# Eboard_Powerboard.net
KiCad netlist of a schematic drawn in EAGLE
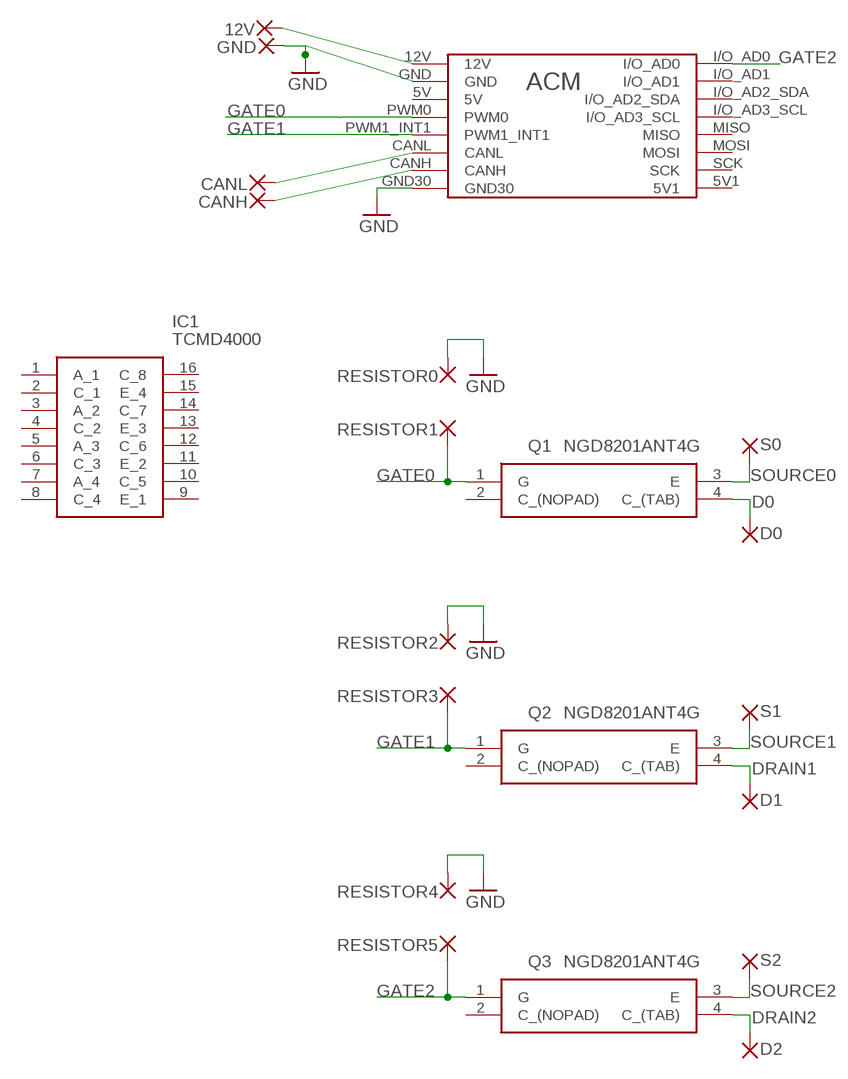
[diagram p0: schematic, sheet 1]

(export (version "E")
  (design (tool "Eeschema 10.0.6"))
  (components
    (comp (ref "12V")
      (value "2,15/1,0")
      (footprint "eagle-import:2,15_1,0")
      (libsource (lib "eagle-import") (part "2,15/1,0"))
    )
    (comp (ref "CANH")
      (value "2,15/1,0")
      (footprint "eagle-import:2,15_1,0")
      (libsource (lib "eagle-import") (part "2,15/1,0"))
    )
    (comp (ref "CANL")
      (value "2,15/1,0")
      (footprint "eagle-import:2,15_1,0")
      (libsource (lib "eagle-import") (part "2,15/1,0"))
    )
    (comp (ref "D0")
      (value "2,54/1,0")
      (footprint "eagle-import:2,54_1,0")
      (libsource (lib "eagle-import") (part "2,54/1,0"))
    )
    (comp (ref "D1")
      (value "2,54/1,0")
      (footprint "eagle-import:2,54_1,0")
      (libsource (lib "eagle-import") (part "2,54/1,0"))
    )
    (comp (ref "D2")
      (value "2,54/1,0")
      (footprint "eagle-import:2,54_1,0")
      (libsource (lib "eagle-import") (part "2,54/1,0"))
    )
    (comp (ref "GND")
      (value "2,15/1,0")
      (footprint "eagle-import:2,15_1,0")
      (libsource (lib "eagle-import") (part "2,15/1,0"))
    )
    (comp (ref "IC1")
      (value "TCMD4000")
      (footprint "eagle-import:SOIC127P695X210-16N")
      (fields (field (name "MOUSER_PART_NUMBER") "782-TCMD4000"))
      (libsource (lib "eagle-import") (part "TCMD4000"))
    )
    (comp (ref "Q1")
      (value "NGD8201ANT4G")
      (footprint "eagle-import:TO229P990X238-4N")
      (fields (field (name "MOUSER_PART_NUMBER") "7470901"))
      (libsource (lib "eagle-import") (part "NGD8201ANT4G"))
    )
    (comp (ref "Q2")
      (value "NGD8201ANT4G")
      (footprint "eagle-import:TO229P990X238-4N")
      (fields (field (name "MOUSER_PART_NUMBER") "7470901"))
      (libsource (lib "eagle-import") (part "NGD8201ANT4G"))
    )
    (comp (ref "Q3")
      (value "NGD8201ANT4G")
      (footprint "eagle-import:TO229P990X238-4N")
      (fields (field (name "MOUSER_PART_NUMBER") "7470901"))
      (libsource (lib "eagle-import") (part "NGD8201ANT4G"))
    )
    (comp (ref "RESISTOR0")
      (value "2,15/1,0")
      (footprint "eagle-import:2,15_1,0")
      (libsource (lib "eagle-import") (part "2,15/1,0"))
    )
    (comp (ref "RESISTOR1")
      (value "2,15/1,0")
      (footprint "eagle-import:2,15_1,0")
      (libsource (lib "eagle-import") (part "2,15/1,0"))
    )
    (comp (ref "RESISTOR2")
      (value "2,15/1,0")
      (footprint "eagle-import:2,15_1,0")
      (libsource (lib "eagle-import") (part "2,15/1,0"))
    )
    (comp (ref "RESISTOR3")
      (value "2,15/1,0")
      (footprint "eagle-import:2,15_1,0")
      (libsource (lib "eagle-import") (part "2,15/1,0"))
    )
    (comp (ref "RESISTOR4")
      (value "2,15/1,0")
      (footprint "eagle-import:2,15_1,0")
      (libsource (lib "eagle-import") (part "2,15/1,0"))
    )
    (comp (ref "RESISTOR5")
      (value "2,15/1,0")
      (footprint "eagle-import:2,15_1,0")
      (libsource (lib "eagle-import") (part "2,15/1,0"))
    )
    (comp (ref "S0")
      (value "2,54/1,0")
      (footprint "eagle-import:2,54_1,0")
      (libsource (lib "eagle-import") (part "2,54/1,0"))
    )
    (comp (ref "S1")
      (value "2,54/1,0")
      (footprint "eagle-import:2,54_1,0")
      (libsource (lib "eagle-import") (part "2,54/1,0"))
    )
    (comp (ref "S2")
      (value "2,54/1,0")
      (footprint "eagle-import:2,54_1,0")
      (libsource (lib "eagle-import") (part "2,54/1,0"))
    )
    (comp (ref "U$1")
      (value "ACM_CASTELLATED")
      (footprint "eagle-import:ACM_CAS_FP")
      (libsource (lib "eagle-import") (part "ACM_CASTELLATED"))
    )
  )
  (nets
    (net (code "1") (name "/D0") (class "Default")
      (node (ref "D0") (pin "1") (pinfunction "P_1") (pintype "passive"))
      (node (ref "Q1") (pin "4") (pinfunction "C_(TAB)_4") (pintype "bidirectional"))
    )
    (net (code "2") (name "/DRAIN1") (class "Default")
      (node (ref "D1") (pin "1") (pinfunction "P_1") (pintype "passive"))
      (node (ref "Q2") (pin "4") (pinfunction "C_(TAB)_4") (pintype "bidirectional"))
    )
    (net (code "3") (name "/DRAIN2") (class "Default")
      (node (ref "D2") (pin "1") (pinfunction "P_1") (pintype "passive"))
      (node (ref "Q3") (pin "4") (pinfunction "C_(TAB)_4") (pintype "bidirectional"))
    )
    (net (code "4") (name "/GATE0") (class "Default")
      (node (ref "Q1") (pin "1") (pinfunction "G_1") (pintype "bidirectional"))
      (node (ref "RESISTOR1") (pin "1") (pinfunction "P_1") (pintype "passive"))
      (node (ref "U$1") (pin "PWM0") (pinfunction "PWM0_PWM0") (pintype "bidirectional"))
    )
    (net (code "5") (name "/GATE1") (class "Default")
      (node (ref "Q2") (pin "1") (pinfunction "G_1") (pintype "bidirectional"))
      (node (ref "RESISTOR3") (pin "1") (pinfunction "P_1") (pintype "passive"))
      (node (ref "U$1") (pin "PWM1_INT1") (pinfunction "PWM1_INT1_PWM1_INT1") (pintype "bidirectional"))
    )
    (net (code "6") (name "/GATE2") (class "Default")
      (node (ref "Q3") (pin "1") (pinfunction "G_1") (pintype "bidirectional"))
      (node (ref "RESISTOR5") (pin "1") (pinfunction "P_1") (pintype "passive"))
      (node (ref "U$1") (pin "I/O_AD0") (pinfunction "I/O_AD0_I/O_AD0") (pintype "bidirectional"))
    )
    (net (code "7") (name "/SOURCE0") (class "Default")
      (node (ref "Q1") (pin "3") (pinfunction "E_3") (pintype "bidirectional"))
      (node (ref "S0") (pin "1") (pinfunction "P_1") (pintype "passive"))
    )
    (net (code "8") (name "/SOURCE1") (class "Default")
      (node (ref "Q2") (pin "3") (pinfunction "E_3") (pintype "bidirectional"))
      (node (ref "S1") (pin "1") (pinfunction "P_1") (pintype "passive"))
    )
    (net (code "9") (name "/SOURCE2") (class "Default")
      (node (ref "Q3") (pin "3") (pinfunction "E_3") (pintype "bidirectional"))
      (node (ref "S2") (pin "1") (pinfunction "P_1") (pintype "passive"))
    )
    (net (code "10") (name "GND") (class "Default")
      (node (ref "GND") (pin "1") (pinfunction "P_1") (pintype "passive"))
      (node (ref "RESISTOR0") (pin "1") (pinfunction "P_1") (pintype "passive"))
      (node (ref "RESISTOR2") (pin "1") (pinfunction "P_1") (pintype "passive"))
      (node (ref "RESISTOR4") (pin "1") (pinfunction "P_1") (pintype "passive"))
      (node (ref "U$1") (pin "GND") (pinfunction "GND_GND") (pintype "bidirectional"))
      (node (ref "U$1") (pin "GND30") (pinfunction "GND30_GND30") (pintype "bidirectional"))
    )
    (net (code "11") (name "Net-(12V-P)") (class "Default")
      (node (ref "12V") (pin "1") (pinfunction "P_1") (pintype "passive"))
      (node (ref "U$1") (pin "12V") (pinfunction "12V_12V") (pintype "bidirectional"))
    )
    (net (code "12") (name "Net-(CANH-P)") (class "Default")
      (node (ref "CANH") (pin "1") (pinfunction "P_1") (pintype "passive"))
      (node (ref "U$1") (pin "CANH") (pinfunction "CANH_CANH") (pintype "bidirectional"))
    )
    (net (code "13") (name "Net-(CANL-P)") (class "Default")
      (node (ref "CANL") (pin "1") (pinfunction "P_1") (pintype "passive"))
      (node (ref "U$1") (pin "CANL") (pinfunction "CANL_CANL") (pintype "bidirectional"))
    )
    (net (code "14") (name "unconnected-(IC1-A_1-Pad1)") (class "Default")
      (node (ref "IC1") (pin "1") (pinfunction "A_1_1") (pintype "bidirectional"))
    )
    (net (code "15") (name "unconnected-(IC1-A_2-Pad3)") (class "Default")
      (node (ref "IC1") (pin "3") (pinfunction "A_2_3") (pintype "bidirectional"))
    )
    (net (code "16") (name "unconnected-(IC1-A_3-Pad5)") (class "Default")
      (node (ref "IC1") (pin "5") (pinfunction "A_3_5") (pintype "bidirectional"))
    )
    (net (code "17") (name "unconnected-(IC1-A_4-Pad7)") (class "Default")
      (node (ref "IC1") (pin "7") (pinfunction "A_4_7") (pintype "bidirectional"))
    )
    (net (code "18") (name "unconnected-(IC1-C_1-Pad2)") (class "Default")
      (node (ref "IC1") (pin "2") (pinfunction "C_1_2") (pintype "bidirectional"))
    )
    (net (code "19") (name "unconnected-(IC1-C_2-Pad4)") (class "Default")
      (node (ref "IC1") (pin "4") (pinfunction "C_2_4") (pintype "bidirectional"))
    )
    (net (code "20") (name "unconnected-(IC1-C_3-Pad6)") (class "Default")
      (node (ref "IC1") (pin "6") (pinfunction "C_3_6") (pintype "bidirectional"))
    )
    (net (code "21") (name "unconnected-(IC1-C_4-Pad8)") (class "Default")
      (node (ref "IC1") (pin "8") (pinfunction "C_4_8") (pintype "bidirectional"))
    )
    (net (code "22") (name "unconnected-(IC1-C_5-Pad10)") (class "Default")
      (node (ref "IC1") (pin "10") (pinfunction "C_5_10") (pintype "bidirectional"))
    )
    (net (code "23") (name "unconnected-(IC1-C_6-Pad12)") (class "Default")
      (node (ref "IC1") (pin "12") (pinfunction "C_6_12") (pintype "bidirectional"))
    )
    (net (code "24") (name "unconnected-(IC1-C_7-Pad14)") (class "Default")
      (node (ref "IC1") (pin "14") (pinfunction "C_7_14") (pintype "bidirectional"))
    )
    (net (code "25") (name "unconnected-(IC1-C_8-Pad16)") (class "Default")
      (node (ref "IC1") (pin "16") (pinfunction "C_8_16") (pintype "bidirectional"))
    )
    (net (code "26") (name "unconnected-(IC1-E_1-Pad9)") (class "Default")
      (node (ref "IC1") (pin "9") (pinfunction "E_1_9") (pintype "bidirectional"))
    )
    (net (code "27") (name "unconnected-(IC1-E_2-Pad11)") (class "Default")
      (node (ref "IC1") (pin "11") (pinfunction "E_2_11") (pintype "bidirectional"))
    )
    (net (code "28") (name "unconnected-(IC1-E_3-Pad13)") (class "Default")
      (node (ref "IC1") (pin "13") (pinfunction "E_3_13") (pintype "bidirectional"))
    )
    (net (code "29") (name "unconnected-(IC1-E_4-Pad15)") (class "Default")
      (node (ref "IC1") (pin "15") (pinfunction "E_4_15") (pintype "bidirectional"))
    )
    (net (code "30") (name "unconnected-(Q1-C_(NOPAD)-Pad2)") (class "Default")
      (node (ref "Q1") (pin "2") (pinfunction "C_(NOPAD)_2") (pintype "bidirectional"))
    )
    (net (code "31") (name "unconnected-(Q2-C_(NOPAD)-Pad2)") (class "Default")
      (node (ref "Q2") (pin "2") (pinfunction "C_(NOPAD)_2") (pintype "bidirectional"))
    )
    (net (code "32") (name "unconnected-(Q3-C_(NOPAD)-Pad2)") (class "Default")
      (node (ref "Q3") (pin "2") (pinfunction "C_(NOPAD)_2") (pintype "bidirectional"))
    )
    (net (code "33") (name "unconnected-(U$1-Pad5V)") (class "Default")
      (node (ref "U$1") (pin "5V") (pinfunction "5V_5V") (pintype "bidirectional"))
    )
    (net (code "34") (name "unconnected-(U$1-Pad5V1)") (class "Default")
      (node (ref "U$1") (pin "5V1") (pinfunction "5V1_5V1") (pintype "bidirectional"))
    )
    (net (code "35") (name "unconnected-(U$1-PadI{slash}O_AD1)") (class "Default")
      (node (ref "U$1") (pin "I/O_AD1") (pinfunction "I/O_AD1_I/O_AD1") (pintype "bidirectional"))
    )
    (net (code "36") (name "unconnected-(U$1-PadI{slash}O_AD2_SDA)") (class "Default")
      (node (ref "U$1") (pin "I/O_AD2_SDA") (pinfunction "I/O_AD2_SDA_I/O_AD2_SDA") (pintype "bidirectional"))
    )
    (net (code "37") (name "unconnected-(U$1-PadI{slash}O_AD3_SCL)") (class "Default")
      (node (ref "U$1") (pin "I/O_AD3_SCL") (pinfunction "I/O_AD3_SCL_I/O_AD3_SCL") (pintype "bidirectional"))
    )
    (net (code "38") (name "unconnected-(U$1-PadMISO)") (class "Default")
      (node (ref "U$1") (pin "MISO") (pinfunction "MISO_MISO") (pintype "bidirectional"))
    )
    (net (code "39") (name "unconnected-(U$1-PadMOSI)") (class "Default")
      (node (ref "U$1") (pin "MOSI") (pinfunction "MOSI_MOSI") (pintype "bidirectional"))
    )
    (net (code "40") (name "unconnected-(U$1-PadSCK)") (class "Default")
      (node (ref "U$1") (pin "SCK") (pinfunction "SCK_SCK") (pintype "bidirectional"))
    )
  )
)
